# LAMP.net
KiCad netlist of a schematic drawn in EAGLE
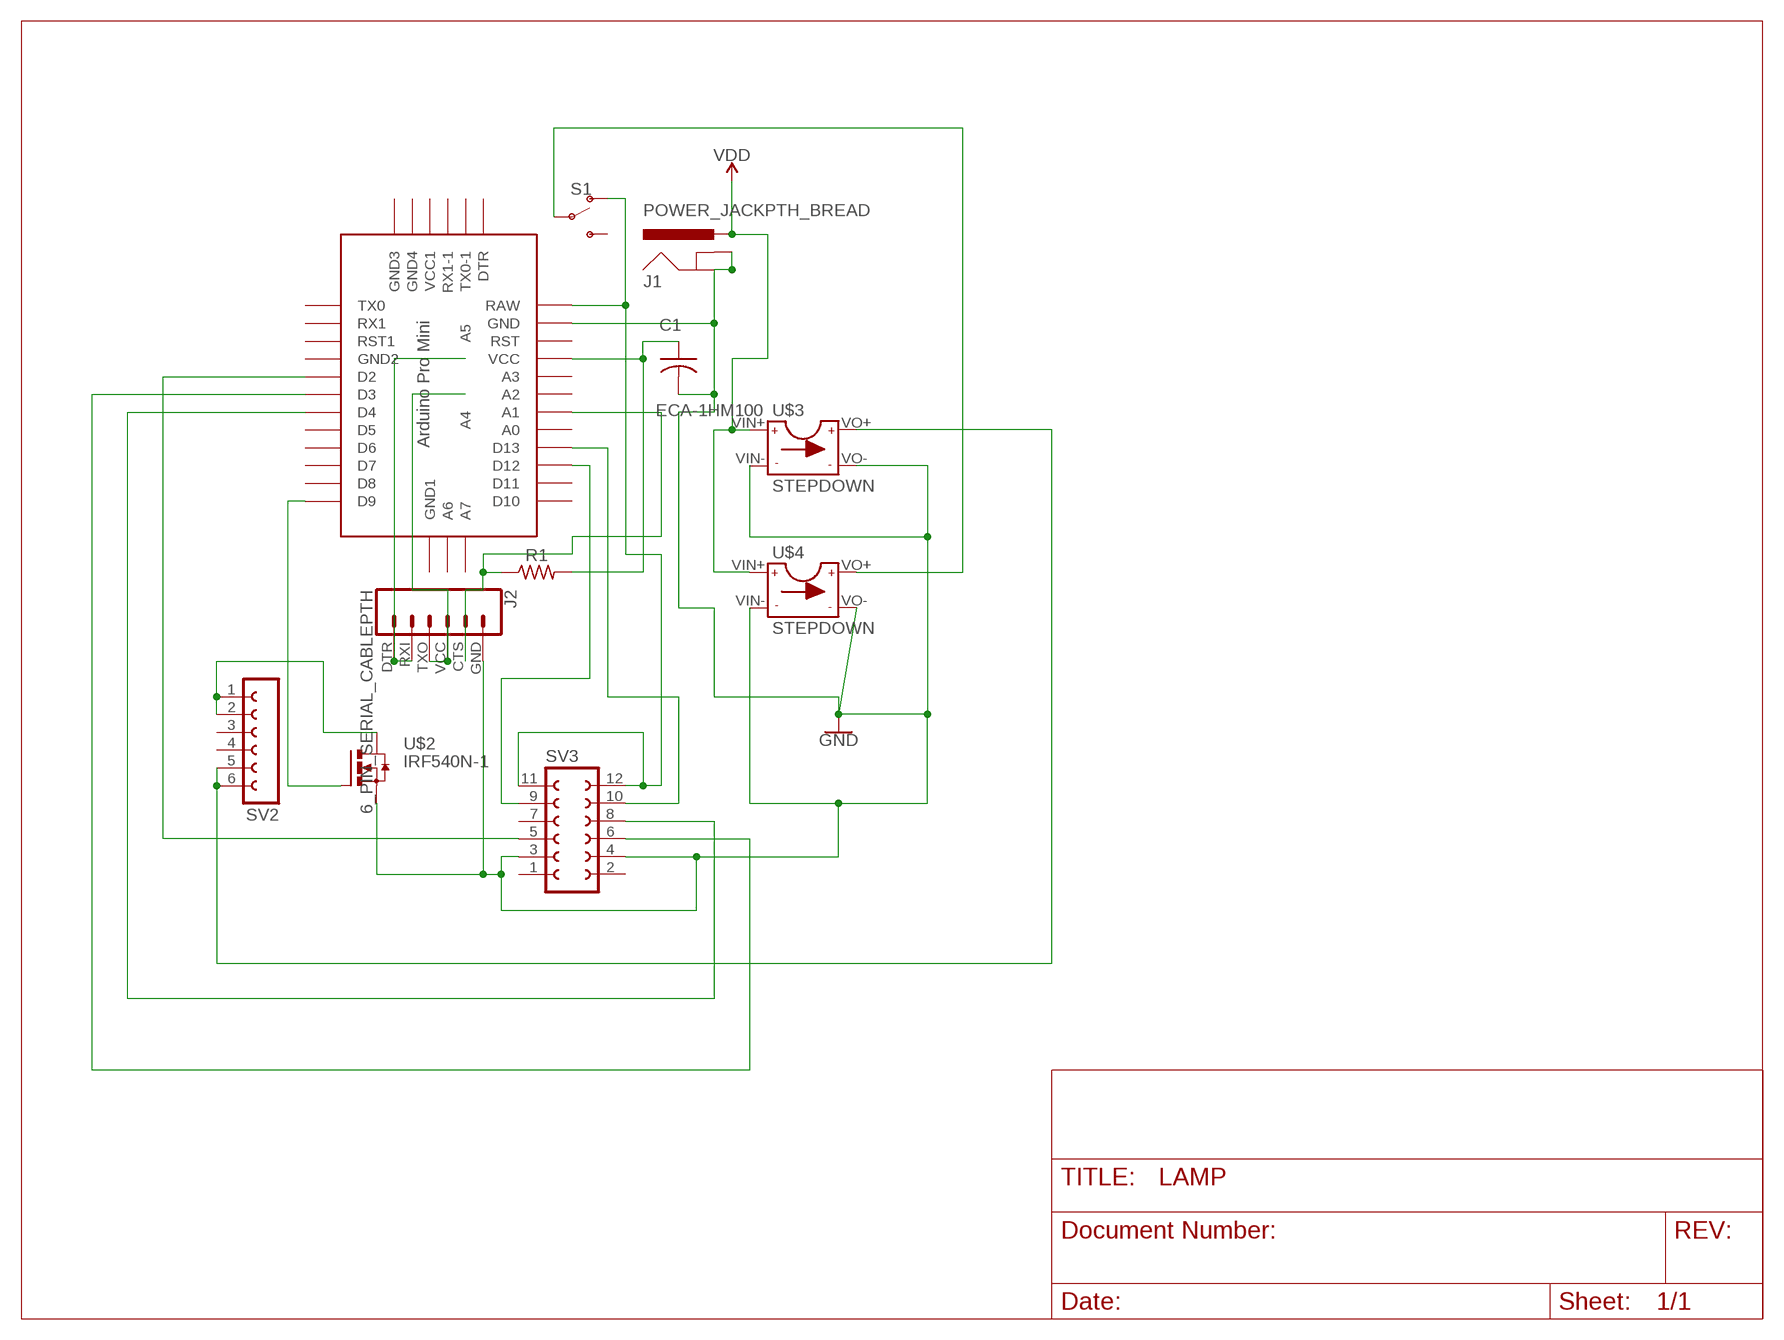
[diagram p0: schematic, sheet 1]

(export (version "E")
  (design (tool "Eeschema 10.0.6"))
  (components
    (comp (ref "C1")
      (value "ECA-1HM100")
      (footprint "eagle-import:CAP_RADIAL_2MM")
      (fields
        (field (name "DIGIKEY_PART_NUMBER") "P5178-ND")
        (field (name "MANUFACTURER") "Panasonic Electronic Components")
        (field (name "CREATED_BY") "PCBLayout.com")
      )
      (libsource (lib "eagle-import") (part "ECA-1HM100"))
    )
    (comp (ref "J1")
      (value "POWER_JACKPTH_BREAD")
      (footprint "eagle-import:POWER_JACK_PTH_BREAD")
      (libsource (lib "eagle-import") (part "POWER_JACKPTH_BREAD"))
    )
    (comp (ref "J2")
      (value "6_PIN_SERIAL_CABLEPTH")
      (footprint "eagle-import:FTDI_BASIC")
      (libsource (lib "eagle-import") (part "6_PIN_SERIAL_CABLEPTH"))
    )
    (comp (ref "R1")
      (value "1k")
      (footprint "eagle-import:V234_12")
      (libsource (lib "eagle-import") (part "R-US_V234/12"))
    )
    (comp (ref "S1")
      (value "SWITCH-SPDT-PTH-11.6X4.0MM")
      (footprint "eagle-import:SWITCH_SPDT_PTH_11.6X4.0MM")
      (libsource (lib "eagle-import") (part "SWITCH-SPDT-PTH-11.6X4.0MM"))
    )
    (comp (ref "SV2")
      (value "FE06-1")
      (footprint "eagle-import:FE06")
      (libsource (lib "eagle-import") (part "FE06-1"))
    )
    (comp (ref "SV3")
      (value "FE06-2")
      (footprint "eagle-import:FE06-2")
      (libsource (lib "eagle-import") (part "FE06-2"))
    )
    (comp (ref "U$1")
      (value "ABK-PRO-MINI-2")
      (footprint "eagle-import:ABK-PRO-MINI-2")
      (libsource (lib "eagle-import") (part "ABK-PRO-MINI-2"))
    )
    (comp (ref "U$2")
      (value "IRF540N-1")
      (footprint "eagle-import:1X03")
      (libsource (lib "eagle-import") (part "IRF540N-1"))
    )
    (comp (ref "U$3")
      (value "STEPDOWN")
      (footprint "eagle-import:STEPDOWN-1")
      (libsource (lib "eagle-import") (part "STEPDOWN"))
    )
    (comp (ref "U$4")
      (value "STEPDOWN")
      (footprint "eagle-import:STEPDOWN-1")
      (libsource (lib "eagle-import") (part "STEPDOWN"))
    )
  )
  (nets
    (net (code "1") (name "GND") (class "Default")
      (node (ref "C1") (pin "2") (pinfunction "2_2") (pintype "passive"))
      (node (ref "J1") (pin "GND") (pinfunction "GND_GND") (pintype "bidirectional"))
      (node (ref "J1") (pin "GNDBREAK") (pinfunction "GNDBREAK_GNDBREAK") (pintype "bidirectional"))
      (node (ref "J2") (pin "GND") (pinfunction "6_GND") (pintype "passive"))
      (node (ref "SV3") (pin "3") (pinfunction "3_3") (pintype "passive"))
      (node (ref "SV3") (pin "4") (pinfunction "4_4") (pintype "passive"))
      (node (ref "U$1") (pin "GND") (pinfunction "GND_GND") (pintype "bidirectional"))
      (node (ref "U$2") (pin "3") (pinfunction "S_3") (pintype "passive"))
      (node (ref "U$3") (pin "VIN-") (pinfunction "VIN-_VIN-") (pintype "passive"))
      (node (ref "U$3") (pin "VO-") (pinfunction "VO-_VO-") (pintype "passive"))
      (node (ref "U$4") (pin "VIN-") (pinfunction "VIN-_VIN-") (pintype "passive"))
      (node (ref "U$4") (pin "VO-") (pinfunction "VO-_VO-") (pintype "passive"))
    )
    (net (code "2") (name "Net-(C1-Pad1)") (class "Default")
      (node (ref "C1") (pin "1") (pinfunction "1_1") (pintype "passive"))
      (node (ref "R1") (pin "2") (pinfunction "2_2") (pintype "passive"))
      (node (ref "U$1") (pin "VCC") (pinfunction "VCC_VCC") (pintype "bidirectional"))
    )
    (net (code "3") (name "Net-(J2-1)") (class "Default")
      (node (ref "J2") (pin "DTR") (pinfunction "1_DTR") (pintype "passive"))
      (node (ref "J2") (pin "RXI") (pinfunction "2_RXI") (pintype "passive"))
      (node (ref "U$1") (pin "A5") (pinfunction "A5_A5") (pintype "bidirectional"))
    )
    (net (code "4") (name "Net-(J2-3)") (class "Default")
      (node (ref "J2") (pin "TXO") (pinfunction "3_TXO") (pintype "passive"))
      (node (ref "J2") (pin "VCC") (pinfunction "4_VCC") (pintype "passive"))
      (node (ref "U$1") (pin "A4") (pinfunction "A4_A4") (pintype "bidirectional"))
    )
    (net (code "5") (name "Net-(J2-5)") (class "Default")
      (node (ref "J2") (pin "CTS") (pinfunction "5_CTS") (pintype "passive"))
      (node (ref "R1") (pin "1") (pinfunction "1_1") (pintype "passive"))
      (node (ref "U$1") (pin "A1") (pinfunction "A1_A1") (pintype "bidirectional"))
    )
    (net (code "6") (name "Net-(S1-O)") (class "Default")
      (node (ref "S1") (pin "1") (pinfunction "O_1") (pintype "passive"))
      (node (ref "SV3") (pin "11") (pinfunction "11_11") (pintype "passive"))
      (node (ref "SV3") (pin "12") (pinfunction "12_12") (pintype "passive"))
      (node (ref "U$1") (pin "RAW") (pinfunction "RAW_RAW") (pintype "bidirectional"))
    )
    (net (code "7") (name "Net-(S1-P)") (class "Default")
      (node (ref "S1") (pin "2") (pinfunction "P_2") (pintype "passive"))
      (node (ref "U$4") (pin "VO+") (pinfunction "VO+_VO+") (pintype "passive"))
    )
    (net (code "8") (name "Net-(SV2-Pad5)") (class "Default")
      (node (ref "SV2") (pin "5") (pinfunction "5_5") (pintype "passive"))
      (node (ref "SV2") (pin "6") (pinfunction "6_6") (pintype "passive"))
      (node (ref "U$3") (pin "VO+") (pinfunction "VO+_VO+") (pintype "passive"))
    )
    (net (code "9") (name "Net-(SV3-Pad5)") (class "Default")
      (node (ref "SV3") (pin "5") (pinfunction "5_5") (pintype "passive"))
      (node (ref "U$1") (pin "D2") (pinfunction "D2_D2") (pintype "bidirectional"))
    )
    (net (code "10") (name "Net-(SV3-Pad6)") (class "Default")
      (node (ref "SV3") (pin "6") (pinfunction "6_6") (pintype "passive"))
      (node (ref "U$1") (pin "D3") (pinfunction "D3_D3") (pintype "bidirectional"))
    )
    (net (code "11") (name "Net-(SV3-Pad8)") (class "Default")
      (node (ref "SV3") (pin "8") (pinfunction "8_8") (pintype "passive"))
      (node (ref "U$1") (pin "D4") (pinfunction "D4_D4") (pintype "bidirectional"))
    )
    (net (code "12") (name "Net-(SV3-Pad9)") (class "Default")
      (node (ref "SV3") (pin "9") (pinfunction "9_9") (pintype "passive"))
      (node (ref "U$1") (pin "D12") (pinfunction "D12_D12") (pintype "bidirectional"))
    )
    (net (code "13") (name "Net-(SV3-Pad10)") (class "Default")
      (node (ref "SV3") (pin "10") (pinfunction "10_10") (pintype "passive"))
      (node (ref "U$1") (pin "D13") (pinfunction "D13_D13") (pintype "bidirectional"))
    )
    (net (code "14") (name "Net-(U$2-D)") (class "Default")
      (node (ref "SV2") (pin "1") (pinfunction "1_1") (pintype "passive"))
      (node (ref "SV2") (pin "2") (pinfunction "2_2") (pintype "passive"))
      (node (ref "U$2") (pin "2") (pinfunction "D_2") (pintype "passive"))
    )
    (net (code "15") (name "Net-(U$2-G)") (class "Default")
      (node (ref "U$1") (pin "D9") (pinfunction "D9_D9") (pintype "bidirectional"))
      (node (ref "U$2") (pin "1") (pinfunction "G_1") (pintype "passive"))
    )
    (net (code "16") (name "VDD") (class "Default")
      (node (ref "J1") (pin "PWR") (pinfunction "PWR_PWR") (pintype "bidirectional"))
      (node (ref "U$3") (pin "VIN+") (pinfunction "VIN+_VIN+") (pintype "passive"))
      (node (ref "U$4") (pin "VIN+") (pinfunction "VIN+_VIN+") (pintype "passive"))
    )
    (net (code "17") (name "unconnected-(S1-S-Pad3)") (class "Default")
      (node (ref "S1") (pin "3") (pinfunction "S_3") (pintype "passive"))
    )
    (net (code "18") (name "unconnected-(SV2-Pad3)") (class "Default")
      (node (ref "SV2") (pin "3") (pinfunction "3_3") (pintype "passive"))
    )
    (net (code "19") (name "unconnected-(SV2-Pad4)") (class "Default")
      (node (ref "SV2") (pin "4") (pinfunction "4_4") (pintype "passive"))
    )
    (net (code "20") (name "unconnected-(SV3-Pad1)") (class "Default")
      (node (ref "SV3") (pin "1") (pinfunction "1_1") (pintype "passive"))
    )
    (net (code "21") (name "unconnected-(SV3-Pad2)") (class "Default")
      (node (ref "SV3") (pin "2") (pinfunction "2_2") (pintype "passive"))
    )
    (net (code "22") (name "unconnected-(SV3-Pad7)") (class "Default")
      (node (ref "SV3") (pin "7") (pinfunction "7_7") (pintype "passive"))
    )
    (net (code "23") (name "unconnected-(U$1-PadA0)") (class "Default")
      (node (ref "U$1") (pin "A0") (pinfunction "A0_A0") (pintype "bidirectional"))
    )
    (net (code "24") (name "unconnected-(U$1-PadA2)") (class "Default")
      (node (ref "U$1") (pin "A2") (pinfunction "A2_A2") (pintype "bidirectional"))
    )
    (net (code "25") (name "unconnected-(U$1-PadA3)") (class "Default")
      (node (ref "U$1") (pin "A3") (pinfunction "A3_A3") (pintype "bidirectional"))
    )
    (net (code "26") (name "unconnected-(U$1-PadA6)") (class "Default")
      (node (ref "U$1") (pin "A6") (pinfunction "A6_A6") (pintype "bidirectional"))
    )
    (net (code "27") (name "unconnected-(U$1-PadA7)") (class "Default")
      (node (ref "U$1") (pin "A7") (pinfunction "A7_A7") (pintype "bidirectional"))
    )
    (net (code "28") (name "unconnected-(U$1-PadD5)") (class "Default")
      (node (ref "U$1") (pin "D5") (pinfunction "D5_D5") (pintype "bidirectional"))
    )
    (net (code "29") (name "unconnected-(U$1-PadD6)") (class "Default")
      (node (ref "U$1") (pin "D6") (pinfunction "D6_D6") (pintype "bidirectional"))
    )
    (net (code "30") (name "unconnected-(U$1-PadD7)") (class "Default")
      (node (ref "U$1") (pin "D7") (pinfunction "D7_D7") (pintype "bidirectional"))
    )
    (net (code "31") (name "unconnected-(U$1-PadD8)") (class "Default")
      (node (ref "U$1") (pin "D8") (pinfunction "D8_D8") (pintype "bidirectional"))
    )
    (net (code "32") (name "unconnected-(U$1-PadD10)") (class "Default")
      (node (ref "U$1") (pin "D10") (pinfunction "D10_D10") (pintype "bidirectional"))
    )
    (net (code "33") (name "unconnected-(U$1-PadD11)") (class "Default")
      (node (ref "U$1") (pin "D11") (pinfunction "D11_D11") (pintype "bidirectional"))
    )
    (net (code "34") (name "unconnected-(U$1-PadDTR)") (class "Default")
      (node (ref "U$1") (pin "DTR") (pinfunction "DTR_DTR") (pintype "bidirectional"))
    )
    (net (code "35") (name "unconnected-(U$1-PadGND1)") (class "Default")
      (node (ref "U$1") (pin "GND1") (pinfunction "GND1_GND1") (pintype "bidirectional"))
    )
    (net (code "36") (name "unconnected-(U$1-PadGND2)") (class "Default")
      (node (ref "U$1") (pin "GND2") (pinfunction "GND2_GND2") (pintype "bidirectional"))
    )
    (net (code "37") (name "unconnected-(U$1-PadGND3)") (class "Default")
      (node (ref "U$1") (pin "GND3") (pinfunction "GND3_GND3") (pintype "bidirectional"))
    )
    (net (code "38") (name "unconnected-(U$1-PadGND4)") (class "Default")
      (node (ref "U$1") (pin "GND4") (pinfunction "GND4_GND4") (pintype "bidirectional"))
    )
    (net (code "39") (name "unconnected-(U$1-PadRST)") (class "Default")
      (node (ref "U$1") (pin "RST") (pinfunction "RST_RST") (pintype "bidirectional"))
    )
    (net (code "40") (name "unconnected-(U$1-PadRST1)") (class "Default")
      (node (ref "U$1") (pin "RST1") (pinfunction "RST1_RST1") (pintype "bidirectional"))
    )
    (net (code "41") (name "unconnected-(U$1-PadRX1)") (class "Default")
      (node (ref "U$1") (pin "RX1") (pinfunction "RX1_RX1") (pintype "bidirectional"))
    )
    (net (code "42") (name "unconnected-(U$1-PadRX1-1)") (class "Default")
      (node (ref "U$1") (pin "RX1-1") (pinfunction "RX1-1_RX1-1") (pintype "bidirectional"))
    )
    (net (code "43") (name "unconnected-(U$1-PadTX0)") (class "Default")
      (node (ref "U$1") (pin "TX0") (pinfunction "TX0_TX0") (pintype "bidirectional"))
    )
    (net (code "44") (name "unconnected-(U$1-PadTX0-1)") (class "Default")
      (node (ref "U$1") (pin "TX0-1") (pinfunction "TX0-1_TX0-1") (pintype "bidirectional"))
    )
    (net (code "45") (name "unconnected-(U$1-PadVCC1)") (class "Default")
      (node (ref "U$1") (pin "VCC1") (pinfunction "VCC1_VCC1") (pintype "bidirectional"))
    )
  )
)
